# PATHOS_FPGA_IO_Ext.net
KiCad netlist of a schematic drawn in Altium Designer
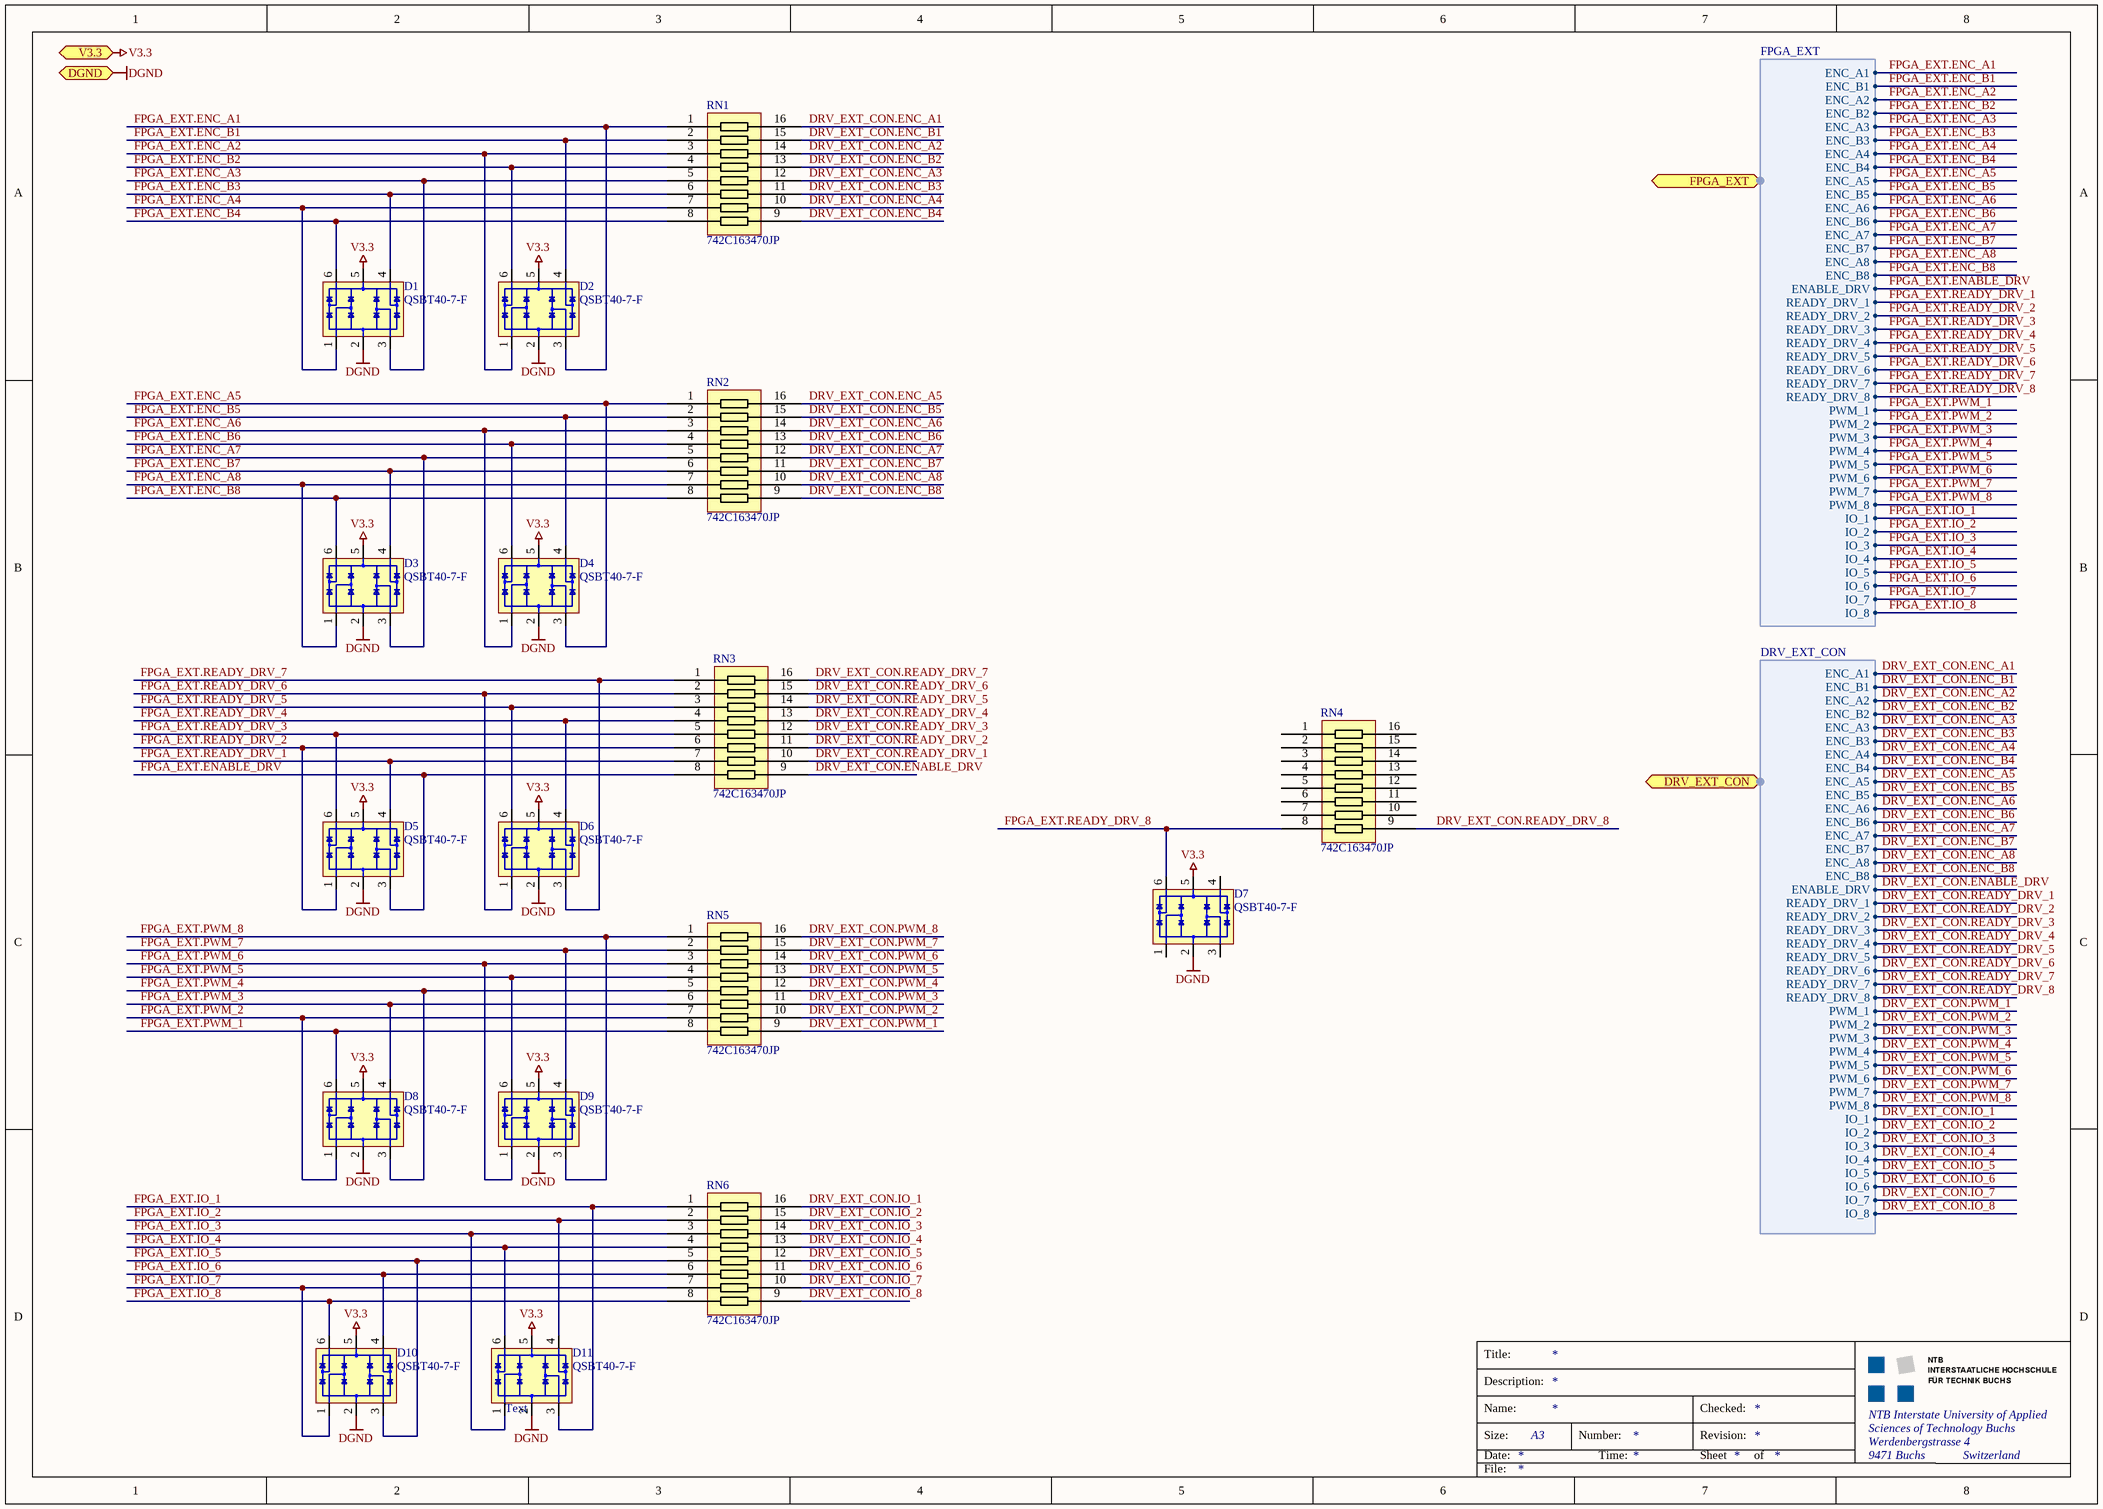
[diagram p0: PATHOS_FPGA_IO_Ext.SchDoc]

(export (version "E")
  (design (tool "Eeschema 10.0.6"))
  (components
    (comp (ref "D1")
      (value "QSBT40-7-F")
      (footprint "SOT363")
      (libsource (lib "PartLib") (part "QSBT40-7-F"))
    )
    (comp (ref "D2")
      (value "QSBT40-7-F")
      (footprint "SOT363")
      (libsource (lib "PartLib") (part "QSBT40-7-F"))
    )
    (comp (ref "D3")
      (value "QSBT40-7-F")
      (footprint "SOT363")
      (libsource (lib "PartLib") (part "QSBT40-7-F"))
    )
    (comp (ref "D4")
      (value "QSBT40-7-F")
      (footprint "SOT363")
      (libsource (lib "PartLib") (part "QSBT40-7-F"))
    )
    (comp (ref "D5")
      (value "QSBT40-7-F")
      (footprint "SOT363")
      (libsource (lib "PartLib") (part "QSBT40-7-F"))
    )
    (comp (ref "D6")
      (value "QSBT40-7-F")
      (footprint "SOT363")
      (libsource (lib "PartLib") (part "QSBT40-7-F"))
    )
    (comp (ref "D7")
      (value "QSBT40-7-F")
      (footprint "SOT363")
      (libsource (lib "PartLib") (part "QSBT40-7-F"))
    )
    (comp (ref "D8")
      (value "QSBT40-7-F")
      (footprint "SOT363")
      (libsource (lib "PartLib") (part "QSBT40-7-F"))
    )
    (comp (ref "D9")
      (value "QSBT40-7-F")
      (footprint "SOT363")
      (libsource (lib "PartLib") (part "QSBT40-7-F"))
    )
    (comp (ref "D10")
      (value "QSBT40-7-F")
      (footprint "SOT363")
      (libsource (lib "PartLib") (part "QSBT40-7-F"))
    )
    (comp (ref "D11")
      (value "QSBT40-7-F")
      (footprint "SOT363")
      (libsource (lib "PartLib") (part "QSBT40-7-F"))
    )
    (comp (ref "RN1")
      (value "742C163470JP")
      (footprint "742C163470JP")
      (libsource (lib "PartLib") (part "742C163470JP"))
    )
    (comp (ref "RN2")
      (value "742C163470JP")
      (footprint "742C163470JP")
      (libsource (lib "PartLib") (part "742C163470JP"))
    )
    (comp (ref "RN3")
      (value "742C163470JP")
      (footprint "742C163470JP")
      (libsource (lib "PartLib") (part "742C163470JP"))
    )
    (comp (ref "RN4")
      (value "742C163470JP")
      (footprint "742C163470JP")
      (libsource (lib "PartLib") (part "742C163470JP"))
    )
    (comp (ref "RN5")
      (value "742C163470JP")
      (footprint "742C163470JP")
      (libsource (lib "PartLib") (part "742C163470JP"))
    )
    (comp (ref "RN6")
      (value "742C163470JP")
      (footprint "742C163470JP")
      (libsource (lib "PartLib") (part "742C163470JP"))
    )
  )
  (nets
    (net (code "3") (name "/DRV_EXT_CON.ENABLE_DRV") (class "Default")
      (node (ref "RN3") (pin "9") (pinfunction "9_9") (pintype "passive"))
    )
    (net (code "4") (name "/DRV_EXT_CON.ENC_A1") (class "Default")
      (node (ref "RN1") (pin "16") (pinfunction "16_16") (pintype "passive"))
    )
    (net (code "5") (name "/DRV_EXT_CON.ENC_A2") (class "Default")
      (node (ref "RN1") (pin "14") (pinfunction "14_14") (pintype "passive"))
    )
    (net (code "6") (name "/DRV_EXT_CON.ENC_A3") (class "Default")
      (node (ref "RN1") (pin "12") (pinfunction "12_12") (pintype "passive"))
    )
    (net (code "7") (name "/DRV_EXT_CON.ENC_A4") (class "Default")
      (node (ref "RN1") (pin "10") (pinfunction "10_10") (pintype "passive"))
    )
    (net (code "8") (name "/DRV_EXT_CON.ENC_A5") (class "Default")
      (node (ref "RN2") (pin "16") (pinfunction "16_16") (pintype "passive"))
    )
    (net (code "9") (name "/DRV_EXT_CON.ENC_A6") (class "Default")
      (node (ref "RN2") (pin "14") (pinfunction "14_14") (pintype "passive"))
    )
    (net (code "10") (name "/DRV_EXT_CON.ENC_A7") (class "Default")
      (node (ref "RN2") (pin "12") (pinfunction "12_12") (pintype "passive"))
    )
    (net (code "11") (name "/DRV_EXT_CON.ENC_A8") (class "Default")
      (node (ref "RN2") (pin "10") (pinfunction "10_10") (pintype "passive"))
    )
    (net (code "12") (name "/DRV_EXT_CON.ENC_B1") (class "Default")
      (node (ref "RN1") (pin "15") (pinfunction "15_15") (pintype "passive"))
    )
    (net (code "13") (name "/DRV_EXT_CON.ENC_B2") (class "Default")
      (node (ref "RN1") (pin "13") (pinfunction "13_13") (pintype "passive"))
    )
    (net (code "14") (name "/DRV_EXT_CON.ENC_B3") (class "Default")
      (node (ref "RN1") (pin "11") (pinfunction "11_11") (pintype "passive"))
    )
    (net (code "15") (name "/DRV_EXT_CON.ENC_B4") (class "Default")
      (node (ref "RN1") (pin "9") (pinfunction "9_9") (pintype "passive"))
    )
    (net (code "16") (name "/DRV_EXT_CON.ENC_B5") (class "Default")
      (node (ref "RN2") (pin "15") (pinfunction "15_15") (pintype "passive"))
    )
    (net (code "17") (name "/DRV_EXT_CON.ENC_B6") (class "Default")
      (node (ref "RN2") (pin "13") (pinfunction "13_13") (pintype "passive"))
    )
    (net (code "18") (name "/DRV_EXT_CON.ENC_B7") (class "Default")
      (node (ref "RN2") (pin "11") (pinfunction "11_11") (pintype "passive"))
    )
    (net (code "19") (name "/DRV_EXT_CON.ENC_B8") (class "Default")
      (node (ref "RN2") (pin "9") (pinfunction "9_9") (pintype "passive"))
    )
    (net (code "20") (name "/DRV_EXT_CON.IO_1") (class "Default")
      (node (ref "RN6") (pin "16") (pinfunction "16_16") (pintype "passive"))
    )
    (net (code "21") (name "/DRV_EXT_CON.IO_2") (class "Default")
      (node (ref "RN6") (pin "15") (pinfunction "15_15") (pintype "passive"))
    )
    (net (code "22") (name "/DRV_EXT_CON.IO_3") (class "Default")
      (node (ref "RN6") (pin "14") (pinfunction "14_14") (pintype "passive"))
    )
    (net (code "23") (name "/DRV_EXT_CON.IO_4") (class "Default")
      (node (ref "RN6") (pin "13") (pinfunction "13_13") (pintype "passive"))
    )
    (net (code "24") (name "/DRV_EXT_CON.IO_5") (class "Default")
      (node (ref "RN6") (pin "12") (pinfunction "12_12") (pintype "passive"))
    )
    (net (code "25") (name "/DRV_EXT_CON.IO_6") (class "Default")
      (node (ref "RN6") (pin "11") (pinfunction "11_11") (pintype "passive"))
    )
    (net (code "26") (name "/DRV_EXT_CON.IO_7") (class "Default")
      (node (ref "RN6") (pin "10") (pinfunction "10_10") (pintype "passive"))
    )
    (net (code "27") (name "/DRV_EXT_CON.IO_8") (class "Default")
      (node (ref "RN6") (pin "9") (pinfunction "9_9") (pintype "passive"))
    )
    (net (code "28") (name "/DRV_EXT_CON.PWM_1") (class "Default")
      (node (ref "RN5") (pin "9") (pinfunction "9_9") (pintype "passive"))
    )
    (net (code "29") (name "/DRV_EXT_CON.PWM_2") (class "Default")
      (node (ref "RN5") (pin "10") (pinfunction "10_10") (pintype "passive"))
    )
    (net (code "30") (name "/DRV_EXT_CON.PWM_3") (class "Default")
      (node (ref "RN5") (pin "11") (pinfunction "11_11") (pintype "passive"))
    )
    (net (code "31") (name "/DRV_EXT_CON.PWM_4") (class "Default")
      (node (ref "RN5") (pin "12") (pinfunction "12_12") (pintype "passive"))
    )
    (net (code "32") (name "/DRV_EXT_CON.PWM_5") (class "Default")
      (node (ref "RN5") (pin "13") (pinfunction "13_13") (pintype "passive"))
    )
    (net (code "33") (name "/DRV_EXT_CON.PWM_6") (class "Default")
      (node (ref "RN5") (pin "14") (pinfunction "14_14") (pintype "passive"))
    )
    (net (code "34") (name "/DRV_EXT_CON.PWM_7") (class "Default")
      (node (ref "RN5") (pin "15") (pinfunction "15_15") (pintype "passive"))
    )
    (net (code "35") (name "/DRV_EXT_CON.PWM_8") (class "Default")
      (node (ref "RN5") (pin "16") (pinfunction "16_16") (pintype "passive"))
    )
    (net (code "36") (name "/DRV_EXT_CON.READY_DRV_1") (class "Default")
      (node (ref "RN3") (pin "10") (pinfunction "10_10") (pintype "passive"))
    )
    (net (code "37") (name "/DRV_EXT_CON.READY_DRV_2") (class "Default")
      (node (ref "RN3") (pin "11") (pinfunction "11_11") (pintype "passive"))
    )
    (net (code "38") (name "/DRV_EXT_CON.READY_DRV_3") (class "Default")
      (node (ref "RN3") (pin "12") (pinfunction "12_12") (pintype "passive"))
    )
    (net (code "39") (name "/DRV_EXT_CON.READY_DRV_4") (class "Default")
      (node (ref "RN3") (pin "13") (pinfunction "13_13") (pintype "passive"))
    )
    (net (code "40") (name "/DRV_EXT_CON.READY_DRV_5") (class "Default")
      (node (ref "RN3") (pin "14") (pinfunction "14_14") (pintype "passive"))
    )
    (net (code "41") (name "/DRV_EXT_CON.READY_DRV_6") (class "Default")
      (node (ref "RN3") (pin "15") (pinfunction "15_15") (pintype "passive"))
    )
    (net (code "42") (name "/DRV_EXT_CON.READY_DRV_7") (class "Default")
      (node (ref "RN3") (pin "16") (pinfunction "16_16") (pintype "passive"))
    )
    (net (code "43") (name "/DRV_EXT_CON.READY_DRV_8") (class "Default")
      (node (ref "RN4") (pin "9") (pinfunction "9_9") (pintype "passive"))
    )
    (net (code "44") (name "/FPGA_EXT.ENABLE_DRV") (class "Default")
      (node (ref "D5") (pin "3") (pinfunction "3_3") (pintype "passive"))
      (node (ref "RN3") (pin "8") (pinfunction "8_8") (pintype "passive"))
    )
    (net (code "45") (name "/FPGA_EXT.ENC_A1") (class "Default")
      (node (ref "D2") (pin "3") (pinfunction "3_3") (pintype "passive"))
      (node (ref "RN1") (pin "1") (pinfunction "1_1") (pintype "passive"))
    )
    (net (code "46") (name "/FPGA_EXT.ENC_A2") (class "Default")
      (node (ref "D2") (pin "1") (pinfunction "1_1") (pintype "passive"))
      (node (ref "RN1") (pin "3") (pinfunction "3_3") (pintype "passive"))
    )
    (net (code "47") (name "/FPGA_EXT.ENC_A3") (class "Default")
      (node (ref "D1") (pin "3") (pinfunction "3_3") (pintype "passive"))
      (node (ref "RN1") (pin "5") (pinfunction "5_5") (pintype "passive"))
    )
    (net (code "48") (name "/FPGA_EXT.ENC_A4") (class "Default")
      (node (ref "D1") (pin "1") (pinfunction "1_1") (pintype "passive"))
      (node (ref "RN1") (pin "7") (pinfunction "7_7") (pintype "passive"))
    )
    (net (code "49") (name "/FPGA_EXT.ENC_A5") (class "Default")
      (node (ref "D4") (pin "3") (pinfunction "3_3") (pintype "passive"))
      (node (ref "RN2") (pin "1") (pinfunction "1_1") (pintype "passive"))
    )
    (net (code "50") (name "/FPGA_EXT.ENC_A6") (class "Default")
      (node (ref "D4") (pin "1") (pinfunction "1_1") (pintype "passive"))
      (node (ref "RN2") (pin "3") (pinfunction "3_3") (pintype "passive"))
    )
    (net (code "51") (name "/FPGA_EXT.ENC_A7") (class "Default")
      (node (ref "D3") (pin "3") (pinfunction "3_3") (pintype "passive"))
      (node (ref "RN2") (pin "5") (pinfunction "5_5") (pintype "passive"))
    )
    (net (code "52") (name "/FPGA_EXT.ENC_A8") (class "Default")
      (node (ref "D3") (pin "1") (pinfunction "1_1") (pintype "passive"))
      (node (ref "RN2") (pin "7") (pinfunction "7_7") (pintype "passive"))
    )
    (net (code "53") (name "/FPGA_EXT.ENC_B1") (class "Default")
      (node (ref "D2") (pin "4") (pinfunction "4_4") (pintype "passive"))
      (node (ref "RN1") (pin "2") (pinfunction "2_2") (pintype "passive"))
    )
    (net (code "54") (name "/FPGA_EXT.ENC_B2") (class "Default")
      (node (ref "D2") (pin "6") (pinfunction "6_6") (pintype "passive"))
      (node (ref "RN1") (pin "4") (pinfunction "4_4") (pintype "passive"))
    )
    (net (code "55") (name "/FPGA_EXT.ENC_B3") (class "Default")
      (node (ref "D1") (pin "4") (pinfunction "4_4") (pintype "passive"))
      (node (ref "RN1") (pin "6") (pinfunction "6_6") (pintype "passive"))
    )
    (net (code "56") (name "/FPGA_EXT.ENC_B4") (class "Default")
      (node (ref "D1") (pin "6") (pinfunction "6_6") (pintype "passive"))
      (node (ref "RN1") (pin "8") (pinfunction "8_8") (pintype "passive"))
    )
    (net (code "57") (name "/FPGA_EXT.ENC_B5") (class "Default")
      (node (ref "D4") (pin "4") (pinfunction "4_4") (pintype "passive"))
      (node (ref "RN2") (pin "2") (pinfunction "2_2") (pintype "passive"))
    )
    (net (code "58") (name "/FPGA_EXT.ENC_B6") (class "Default")
      (node (ref "D4") (pin "6") (pinfunction "6_6") (pintype "passive"))
      (node (ref "RN2") (pin "4") (pinfunction "4_4") (pintype "passive"))
    )
    (net (code "59") (name "/FPGA_EXT.ENC_B7") (class "Default")
      (node (ref "D3") (pin "4") (pinfunction "4_4") (pintype "passive"))
      (node (ref "RN2") (pin "6") (pinfunction "6_6") (pintype "passive"))
    )
    (net (code "60") (name "/FPGA_EXT.ENC_B8") (class "Default")
      (node (ref "D3") (pin "6") (pinfunction "6_6") (pintype "passive"))
      (node (ref "RN2") (pin "8") (pinfunction "8_8") (pintype "passive"))
    )
    (net (code "61") (name "/FPGA_EXT.IO_1") (class "Default")
      (node (ref "D11") (pin "3") (pinfunction "3_3") (pintype "passive"))
      (node (ref "RN6") (pin "1") (pinfunction "1_1") (pintype "passive"))
    )
    (net (code "62") (name "/FPGA_EXT.IO_2") (class "Default")
      (node (ref "D11") (pin "4") (pinfunction "4_4") (pintype "passive"))
      (node (ref "RN6") (pin "2") (pinfunction "2_2") (pintype "passive"))
    )
    (net (code "63") (name "/FPGA_EXT.IO_3") (class "Default")
      (node (ref "D11") (pin "1") (pinfunction "1_1") (pintype "passive"))
      (node (ref "RN6") (pin "3") (pinfunction "3_3") (pintype "passive"))
    )
    (net (code "64") (name "/FPGA_EXT.IO_4") (class "Default")
      (node (ref "D11") (pin "6") (pinfunction "6_6") (pintype "passive"))
      (node (ref "RN6") (pin "4") (pinfunction "4_4") (pintype "passive"))
    )
    (net (code "65") (name "/FPGA_EXT.IO_5") (class "Default")
      (node (ref "D10") (pin "3") (pinfunction "3_3") (pintype "passive"))
      (node (ref "RN6") (pin "5") (pinfunction "5_5") (pintype "passive"))
    )
    (net (code "66") (name "/FPGA_EXT.IO_6") (class "Default")
      (node (ref "D10") (pin "4") (pinfunction "4_4") (pintype "passive"))
      (node (ref "RN6") (pin "6") (pinfunction "6_6") (pintype "passive"))
    )
    (net (code "67") (name "/FPGA_EXT.IO_7") (class "Default")
      (node (ref "D10") (pin "1") (pinfunction "1_1") (pintype "passive"))
      (node (ref "RN6") (pin "7") (pinfunction "7_7") (pintype "passive"))
    )
    (net (code "68") (name "/FPGA_EXT.IO_8") (class "Default")
      (node (ref "D10") (pin "6") (pinfunction "6_6") (pintype "passive"))
      (node (ref "RN6") (pin "8") (pinfunction "8_8") (pintype "passive"))
    )
    (net (code "69") (name "/FPGA_EXT.PWM_1") (class "Default")
      (node (ref "D8") (pin "6") (pinfunction "6_6") (pintype "passive"))
      (node (ref "RN5") (pin "8") (pinfunction "8_8") (pintype "passive"))
    )
    (net (code "70") (name "/FPGA_EXT.PWM_2") (class "Default")
      (node (ref "D8") (pin "1") (pinfunction "1_1") (pintype "passive"))
      (node (ref "RN5") (pin "7") (pinfunction "7_7") (pintype "passive"))
    )
    (net (code "71") (name "/FPGA_EXT.PWM_3") (class "Default")
      (node (ref "D8") (pin "4") (pinfunction "4_4") (pintype "passive"))
      (node (ref "RN5") (pin "6") (pinfunction "6_6") (pintype "passive"))
    )
    (net (code "72") (name "/FPGA_EXT.PWM_4") (class "Default")
      (node (ref "D8") (pin "3") (pinfunction "3_3") (pintype "passive"))
      (node (ref "RN5") (pin "5") (pinfunction "5_5") (pintype "passive"))
    )
    (net (code "73") (name "/FPGA_EXT.PWM_5") (class "Default")
      (node (ref "D9") (pin "6") (pinfunction "6_6") (pintype "passive"))
      (node (ref "RN5") (pin "4") (pinfunction "4_4") (pintype "passive"))
    )
    (net (code "74") (name "/FPGA_EXT.PWM_6") (class "Default")
      (node (ref "D9") (pin "1") (pinfunction "1_1") (pintype "passive"))
      (node (ref "RN5") (pin "3") (pinfunction "3_3") (pintype "passive"))
    )
    (net (code "75") (name "/FPGA_EXT.PWM_7") (class "Default")
      (node (ref "D9") (pin "4") (pinfunction "4_4") (pintype "passive"))
      (node (ref "RN5") (pin "2") (pinfunction "2_2") (pintype "passive"))
    )
    (net (code "76") (name "/FPGA_EXT.PWM_8") (class "Default")
      (node (ref "D9") (pin "3") (pinfunction "3_3") (pintype "passive"))
      (node (ref "RN5") (pin "1") (pinfunction "1_1") (pintype "passive"))
    )
    (net (code "77") (name "/FPGA_EXT.READY_DRV_1") (class "Default")
      (node (ref "D5") (pin "4") (pinfunction "4_4") (pintype "passive"))
      (node (ref "RN3") (pin "7") (pinfunction "7_7") (pintype "passive"))
    )
    (net (code "78") (name "/FPGA_EXT.READY_DRV_2") (class "Default")
      (node (ref "D5") (pin "1") (pinfunction "1_1") (pintype "passive"))
      (node (ref "RN3") (pin "6") (pinfunction "6_6") (pintype "passive"))
    )
    (net (code "79") (name "/FPGA_EXT.READY_DRV_3") (class "Default")
      (node (ref "D5") (pin "6") (pinfunction "6_6") (pintype "passive"))
      (node (ref "RN3") (pin "5") (pinfunction "5_5") (pintype "passive"))
    )
    (net (code "80") (name "/FPGA_EXT.READY_DRV_4") (class "Default")
      (node (ref "D6") (pin "4") (pinfunction "4_4") (pintype "passive"))
      (node (ref "RN3") (pin "4") (pinfunction "4_4") (pintype "passive"))
    )
    (net (code "81") (name "/FPGA_EXT.READY_DRV_5") (class "Default")
      (node (ref "D6") (pin "6") (pinfunction "6_6") (pintype "passive"))
      (node (ref "RN3") (pin "3") (pinfunction "3_3") (pintype "passive"))
    )
    (net (code "82") (name "/FPGA_EXT.READY_DRV_6") (class "Default")
      (node (ref "D6") (pin "1") (pinfunction "1_1") (pintype "passive"))
      (node (ref "RN3") (pin "2") (pinfunction "2_2") (pintype "passive"))
    )
    (net (code "83") (name "/FPGA_EXT.READY_DRV_7") (class "Default")
      (node (ref "D6") (pin "3") (pinfunction "3_3") (pintype "passive"))
      (node (ref "RN3") (pin "1") (pinfunction "1_1") (pintype "passive"))
    )
    (net (code "84") (name "/FPGA_EXT.READY_DRV_8") (class "Default")
      (node (ref "D7") (pin "6") (pinfunction "6_6") (pintype "passive"))
      (node (ref "RN4") (pin "8") (pinfunction "8_8") (pintype "passive"))
    )
    (net (code "87") (name "DGND") (class "Default")
      (node (ref "D1") (pin "2") (pinfunction "2_2") (pintype "passive"))
      (node (ref "D10") (pin "2") (pinfunction "2_2") (pintype "passive"))
      (node (ref "D11") (pin "2") (pinfunction "2_2") (pintype "passive"))
      (node (ref "D2") (pin "2") (pinfunction "2_2") (pintype "passive"))
      (node (ref "D3") (pin "2") (pinfunction "2_2") (pintype "passive"))
      (node (ref "D4") (pin "2") (pinfunction "2_2") (pintype "passive"))
      (node (ref "D5") (pin "2") (pinfunction "2_2") (pintype "passive"))
      (node (ref "D6") (pin "2") (pinfunction "2_2") (pintype "passive"))
      (node (ref "D7") (pin "2") (pinfunction "2_2") (pintype "passive"))
      (node (ref "D8") (pin "2") (pinfunction "2_2") (pintype "passive"))
      (node (ref "D9") (pin "2") (pinfunction "2_2") (pintype "passive"))
    )
    (net (code "88") (name "V3.3") (class "Default")
      (node (ref "D1") (pin "5") (pinfunction "5_5") (pintype "passive"))
      (node (ref "D10") (pin "5") (pinfunction "5_5") (pintype "passive"))
      (node (ref "D11") (pin "5") (pinfunction "5_5") (pintype "passive"))
      (node (ref "D2") (pin "5") (pinfunction "5_5") (pintype "passive"))
      (node (ref "D3") (pin "5") (pinfunction "5_5") (pintype "passive"))
      (node (ref "D4") (pin "5") (pinfunction "5_5") (pintype "passive"))
      (node (ref "D5") (pin "5") (pinfunction "5_5") (pintype "passive"))
      (node (ref "D6") (pin "5") (pinfunction "5_5") (pintype "passive"))
      (node (ref "D7") (pin "5") (pinfunction "5_5") (pintype "passive"))
      (node (ref "D8") (pin "5") (pinfunction "5_5") (pintype "passive"))
      (node (ref "D9") (pin "5") (pinfunction "5_5") (pintype "passive"))
    )
    (net (code "89") (name "unconnected-(D7-Pad1)") (class "Default")
      (node (ref "D7") (pin "1") (pinfunction "1_1") (pintype "passive"))
    )
    (net (code "90") (name "unconnected-(D7-Pad3)") (class "Default")
      (node (ref "D7") (pin "3") (pinfunction "3_3") (pintype "passive"))
    )
    (net (code "91") (name "unconnected-(D7-Pad4)") (class "Default")
      (node (ref "D7") (pin "4") (pinfunction "4_4") (pintype "passive"))
    )
    (net (code "92") (name "unconnected-(RN4-Pad1)") (class "Default")
      (node (ref "RN4") (pin "1") (pinfunction "1_1") (pintype "passive"))
    )
    (net (code "93") (name "unconnected-(RN4-Pad2)") (class "Default")
      (node (ref "RN4") (pin "2") (pinfunction "2_2") (pintype "passive"))
    )
    (net (code "94") (name "unconnected-(RN4-Pad3)") (class "Default")
      (node (ref "RN4") (pin "3") (pinfunction "3_3") (pintype "passive"))
    )
    (net (code "95") (name "unconnected-(RN4-Pad4)") (class "Default")
      (node (ref "RN4") (pin "4") (pinfunction "4_4") (pintype "passive"))
    )
    (net (code "96") (name "unconnected-(RN4-Pad5)") (class "Default")
      (node (ref "RN4") (pin "5") (pinfunction "5_5") (pintype "passive"))
    )
    (net (code "97") (name "unconnected-(RN4-Pad6)") (class "Default")
      (node (ref "RN4") (pin "6") (pinfunction "6_6") (pintype "passive"))
    )
    (net (code "98") (name "unconnected-(RN4-Pad7)") (class "Default")
      (node (ref "RN4") (pin "7") (pinfunction "7_7") (pintype "passive"))
    )
    (net (code "99") (name "unconnected-(RN4-Pad10)") (class "Default")
      (node (ref "RN4") (pin "10") (pinfunction "10_10") (pintype "passive"))
    )
    (net (code "100") (name "unconnected-(RN4-Pad11)") (class "Default")
      (node (ref "RN4") (pin "11") (pinfunction "11_11") (pintype "passive"))
    )
    (net (code "101") (name "unconnected-(RN4-Pad12)") (class "Default")
      (node (ref "RN4") (pin "12") (pinfunction "12_12") (pintype "passive"))
    )
    (net (code "102") (name "unconnected-(RN4-Pad13)") (class "Default")
      (node (ref "RN4") (pin "13") (pinfunction "13_13") (pintype "passive"))
    )
    (net (code "103") (name "unconnected-(RN4-Pad14)") (class "Default")
      (node (ref "RN4") (pin "14") (pinfunction "14_14") (pintype "passive"))
    )
    (net (code "104") (name "unconnected-(RN4-Pad15)") (class "Default")
      (node (ref "RN4") (pin "15") (pinfunction "15_15") (pintype "passive"))
    )
    (net (code "105") (name "unconnected-(RN4-Pad16)") (class "Default")
      (node (ref "RN4") (pin "16") (pinfunction "16_16") (pintype "passive"))
    )
  )
)
